# yard-ice-2-fpga.net
KiCad netlist of a schematic drawn in Altium Designer
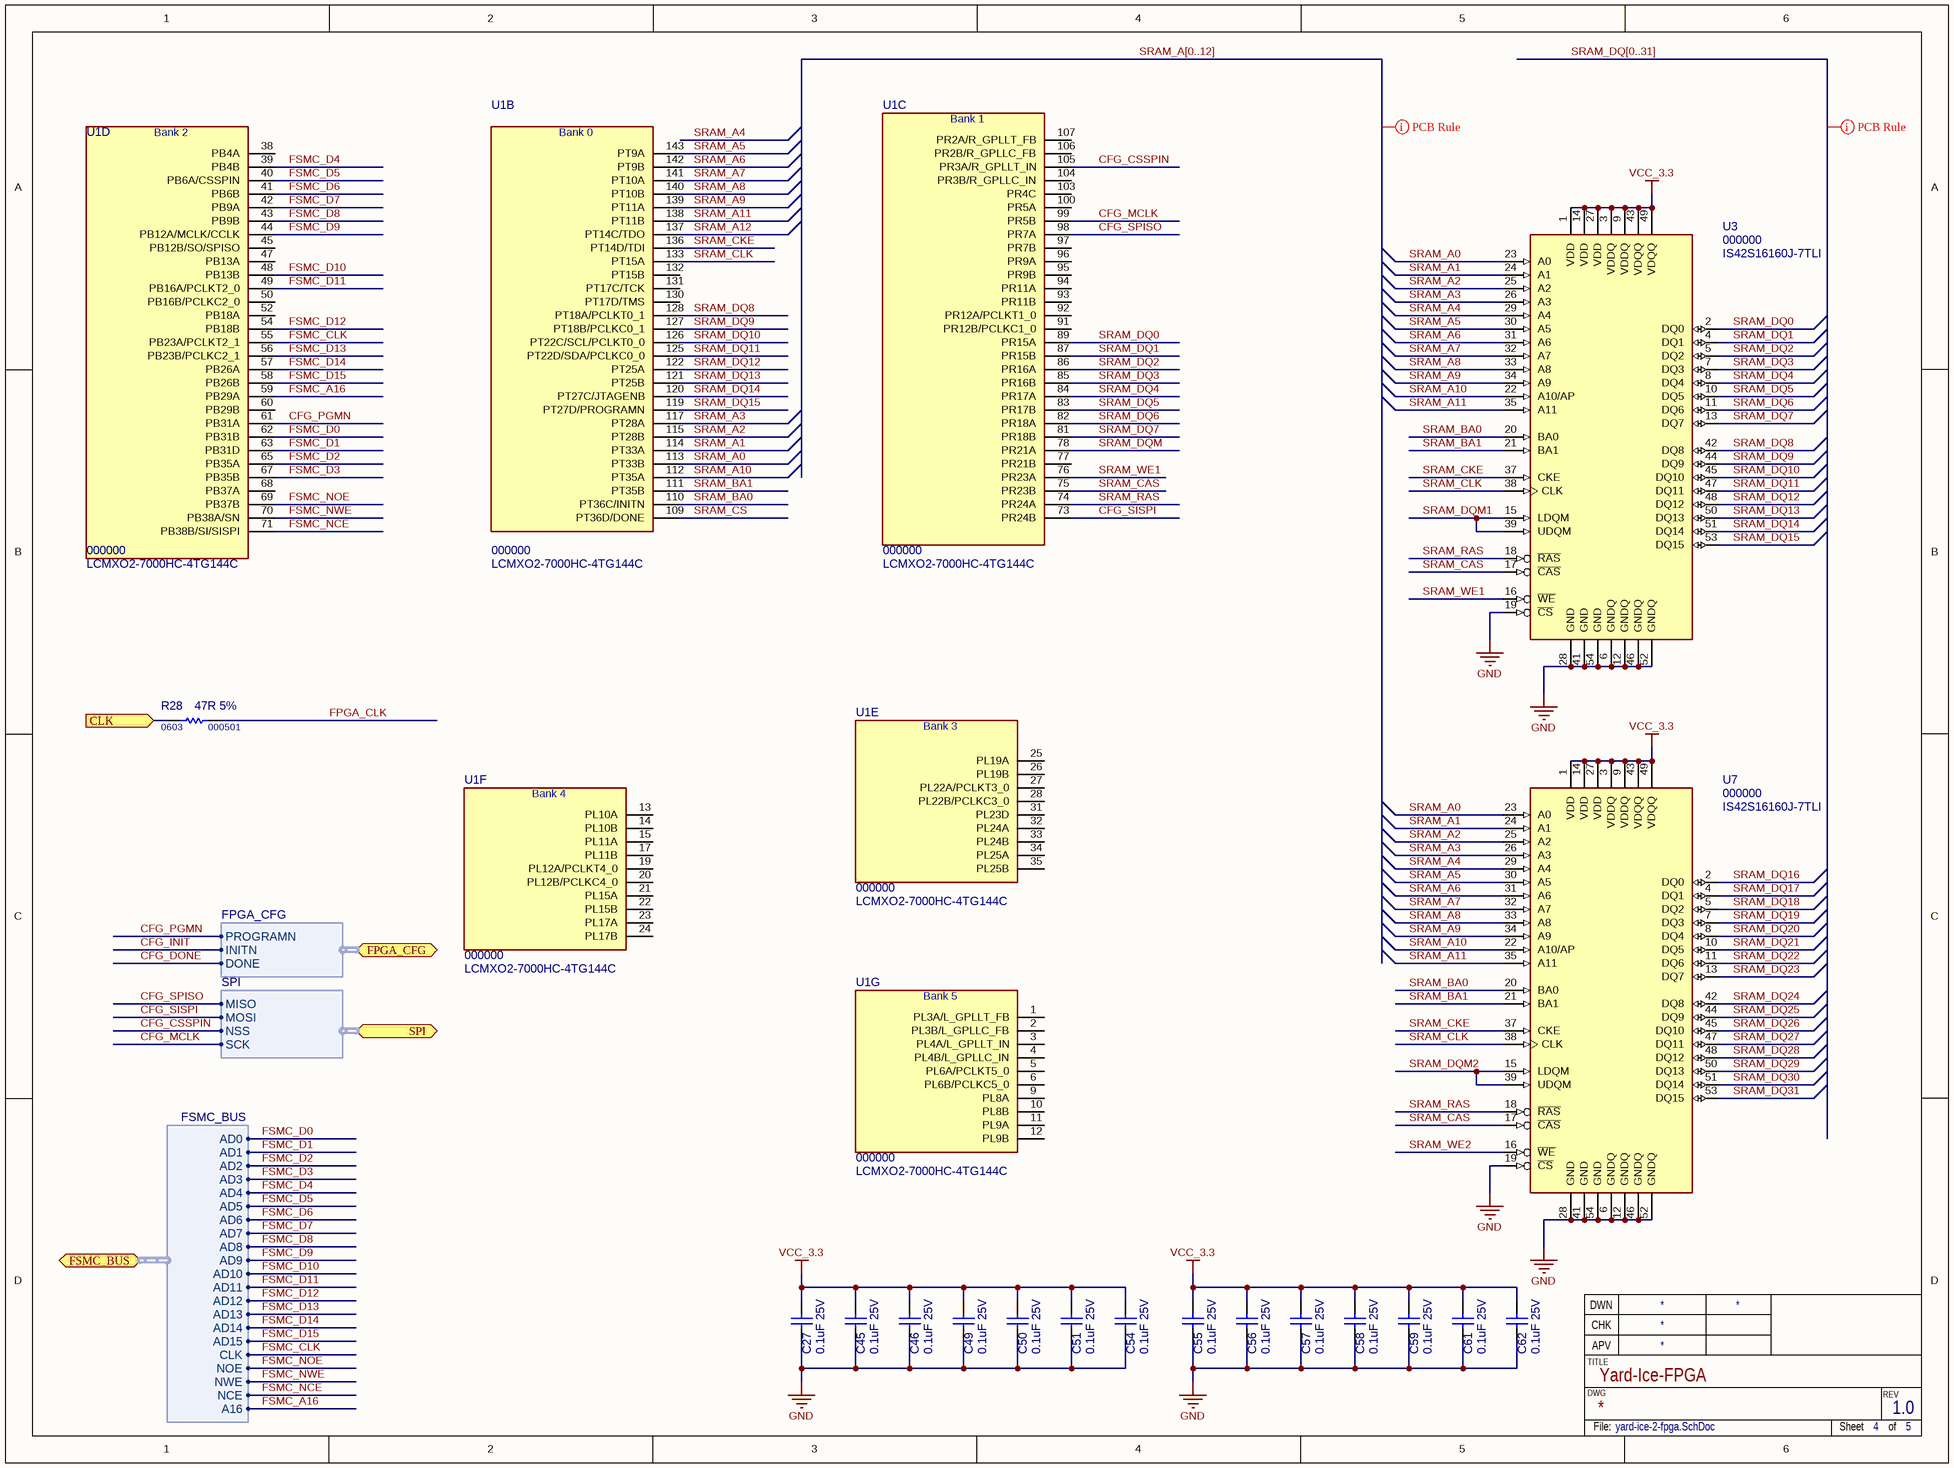
[diagram p0: yard-ice-2-fpga.SchDoc]

(export (version "E")
  (design (tool "Eeschema 10.0.6"))
  (components
    (comp (ref "C27")
      (value "0.1uF 25V")
      (footprint "C0603M")
      (description "SMD Ceramic Chip Capacitor - 0603 - X7R")
      (fields (field (name "MF") "TDK") (field (name "Comment") "000500"))
      (libsource (lib "discrete-sm") (part "C0603"))
    )
    (comp (ref "C45")
      (value "0.1uF 25V")
      (footprint "C0603M")
      (description "SMD Ceramic Chip Capacitor - 0603 - X7R")
      (fields (field (name "MF") "TDK") (field (name "Comment") "000500"))
      (libsource (lib "discrete-sm") (part "C0603"))
    )
    (comp (ref "C46")
      (value "0.1uF 25V")
      (footprint "C0603M")
      (description "SMD Ceramic Chip Capacitor - 0603 - X7R")
      (fields (field (name "MF") "TDK") (field (name "Comment") "000500"))
      (libsource (lib "discrete-sm") (part "C0603"))
    )
    (comp (ref "C49")
      (value "0.1uF 25V")
      (footprint "C0603M")
      (description "SMD Ceramic Chip Capacitor - 0603 - X7R")
      (fields (field (name "MF") "TDK") (field (name "Comment") "000500"))
      (libsource (lib "discrete-sm") (part "C0603"))
    )
    (comp (ref "C50")
      (value "0.1uF 25V")
      (footprint "C0603M")
      (description "SMD Ceramic Chip Capacitor - 0603 - X7R")
      (fields (field (name "MF") "TDK") (field (name "Comment") "000500"))
      (libsource (lib "discrete-sm") (part "C0603"))
    )
    (comp (ref "C51")
      (value "0.1uF 25V")
      (footprint "C0603M")
      (description "SMD Ceramic Chip Capacitor - 0603 - X7R")
      (fields (field (name "MF") "TDK") (field (name "Comment") "000500"))
      (libsource (lib "discrete-sm") (part "C0603"))
    )
    (comp (ref "C54")
      (value "0.1uF 25V")
      (footprint "C0603M")
      (description "SMD Ceramic Chip Capacitor - 0603 - X7R")
      (fields (field (name "MF") "TDK") (field (name "Comment") "000500"))
      (libsource (lib "discrete-sm") (part "C0603"))
    )
    (comp (ref "C55")
      (value "0.1uF 25V")
      (footprint "C0603M")
      (description "SMD Ceramic Chip Capacitor - 0603 - X7R")
      (fields (field (name "MF") "TDK") (field (name "Comment") "000500"))
      (libsource (lib "discrete-sm") (part "C0603"))
    )
    (comp (ref "C56")
      (value "0.1uF 25V")
      (footprint "C0603M")
      (description "SMD Ceramic Chip Capacitor - 0603 - X7R")
      (fields (field (name "MF") "TDK") (field (name "Comment") "000500"))
      (libsource (lib "discrete-sm") (part "C0603"))
    )
    (comp (ref "C57")
      (value "0.1uF 25V")
      (footprint "C0603M")
      (description "SMD Ceramic Chip Capacitor - 0603 - X7R")
      (fields (field (name "MF") "TDK") (field (name "Comment") "000500"))
      (libsource (lib "discrete-sm") (part "C0603"))
    )
    (comp (ref "C58")
      (value "0.1uF 25V")
      (footprint "C0603M")
      (description "SMD Ceramic Chip Capacitor - 0603 - X7R")
      (fields (field (name "MF") "TDK") (field (name "Comment") "000500"))
      (libsource (lib "discrete-sm") (part "C0603"))
    )
    (comp (ref "C59")
      (value "0.1uF 25V")
      (footprint "C0603M")
      (description "SMD Ceramic Chip Capacitor - 0603 - X7R")
      (fields (field (name "MF") "TDK") (field (name "Comment") "000500"))
      (libsource (lib "discrete-sm") (part "C0603"))
    )
    (comp (ref "C61")
      (value "0.1uF 25V")
      (footprint "C0603M")
      (description "SMD Ceramic Chip Capacitor - 0603 - X7R")
      (fields (field (name "MF") "TDK") (field (name "Comment") "000500"))
      (libsource (lib "discrete-sm") (part "C0603"))
    )
    (comp (ref "C62")
      (value "0.1uF 25V")
      (footprint "C0603M")
      (description "SMD Ceramic Chip Capacitor - 0603 - X7R")
      (fields (field (name "MF") "TDK") (field (name "Comment") "000500"))
      (libsource (lib "discrete-sm") (part "C0603"))
    )
    (comp (ref "R28")
      (value "000501")
      (footprint "R0603M")
      (description "SMD Chip Resistor - 0603")
      (fields (field (name "ALTIUM_VALUE") "47R 5%") (field (name "PACKAGE") "0603"))
      (libsource (lib "discrete-sm") (part "R0603"))
    )
    (comp (ref "U1")
      (value "000000")
      (footprint "144-TQFP")
      (description "FPGA, 6864 Logic Elements, Flash")
      (fields (field (name "MF") "Lattice") (field (name "ALTIUM_VALUE") "LCMXO2-7000HC-4TG144C"))
      (libsource (lib "lattice-fpga") (part "LCMXO2-7000HC"))
    )
    (comp (ref "U3")
      (value "000000")
      (footprint "TSOP-54-II")
      (description "256Mbit (16M x16) 143MHz SDRAM")
      (fields (field (name "MF") "ISSI") (field (name "ALTIUM_VALUE") "IS42S16160J-7TLI"))
      (libsource (lib "issi") (part "IS42S16160J-7TL"))
    )
    (comp (ref "U7")
      (value "000000")
      (footprint "TSOP-54-II")
      (description "256Mbit (16M x16) 143MHz SDRAM")
      (fields (field (name "MF") "ISSI") (field (name "ALTIUM_VALUE") "IS42S16160J-7TLI"))
      (libsource (lib "issi") (part "IS42S16160J-7TL"))
    )
  )
  (nets
    (net (code "4") (name "/CFG_CSSPIN") (class "Default")
      (node (ref "U1") (pin "105") (pinfunction "PR3A/R_GPLLT_IN_105") (pintype "passive"))
    )
    (net (code "7") (name "/CFG_MCLK") (class "Default")
      (node (ref "U1") (pin "99") (pinfunction "PR5B_99") (pintype "passive"))
    )
    (net (code "8") (name "/CFG_PGMN") (class "Default")
      (node (ref "U1") (pin "61") (pinfunction "PB31A_61") (pintype "power_in"))
    )
    (net (code "9") (name "/CFG_SISPI") (class "Default")
      (node (ref "U1") (pin "73") (pinfunction "PR24B_73") (pintype "passive"))
    )
    (net (code "10") (name "/CFG_SPISO") (class "Default")
      (node (ref "U1") (pin "98") (pinfunction "PR7A_98") (pintype "passive"))
    )
    (net (code "11") (name "/CLK") (class "Default")
      (node (ref "R28") (pin "2") (pinfunction "2_2") (pintype "passive"))
    )
    (net (code "12") (name "/FPGA_CLK") (class "Default")
      (node (ref "R28") (pin "1") (pinfunction "1_1") (pintype "passive"))
    )
    (net (code "13") (name "/FSMC_A16") (class "Default")
      (node (ref "U1") (pin "59") (pinfunction "PB29A_59") (pintype "passive"))
    )
    (net (code "14") (name "/FSMC_CLK") (class "Default")
      (node (ref "U1") (pin "55") (pinfunction "PB23A/PCLKT2_1_55") (pintype "power_in"))
    )
    (net (code "15") (name "/FSMC_D0") (class "Default")
      (node (ref "U1") (pin "62") (pinfunction "PB31B_62") (pintype "passive"))
    )
    (net (code "16") (name "/FSMC_D1") (class "Default")
      (node (ref "U1") (pin "63") (pinfunction "PB31D_63") (pintype "passive"))
    )
    (net (code "17") (name "/FSMC_D2") (class "Default")
      (node (ref "U1") (pin "65") (pinfunction "PB35A_65") (pintype "passive"))
    )
    (net (code "18") (name "/FSMC_D3") (class "Default")
      (node (ref "U1") (pin "67") (pinfunction "PB35B_67") (pintype "power_in"))
    )
    (net (code "19") (name "/FSMC_D4") (class "Default")
      (node (ref "U1") (pin "39") (pinfunction "PB4B_39") (pintype "power_in"))
    )
    (net (code "20") (name "/FSMC_D5") (class "Default")
      (node (ref "U1") (pin "40") (pinfunction "PB6A/CSSPIN_40") (pintype "passive"))
    )
    (net (code "21") (name "/FSMC_D6") (class "Default")
      (node (ref "U1") (pin "41") (pinfunction "PB6B_41") (pintype "passive"))
    )
    (net (code "22") (name "/FSMC_D7") (class "Default")
      (node (ref "U1") (pin "42") (pinfunction "PB9A_42") (pintype "passive"))
    )
    (net (code "23") (name "/FSMC_D8") (class "Default")
      (node (ref "U1") (pin "43") (pinfunction "PB9B_43") (pintype "passive"))
    )
    (net (code "24") (name "/FSMC_D9") (class "Default")
      (node (ref "U1") (pin "44") (pinfunction "PB12A/MCLK/CCLK_44") (pintype "passive"))
    )
    (net (code "25") (name "/FSMC_D10") (class "Default")
      (node (ref "U1") (pin "48") (pinfunction "PB13B_48") (pintype "passive"))
    )
    (net (code "26") (name "/FSMC_D11") (class "Default")
      (node (ref "U1") (pin "49") (pinfunction "PB16A/PCLKT2_0_49") (pintype "passive"))
    )
    (net (code "27") (name "/FSMC_D12") (class "Default")
      (node (ref "U1") (pin "54") (pinfunction "PB18B_54") (pintype "passive"))
    )
    (net (code "28") (name "/FSMC_D13") (class "Default")
      (node (ref "U1") (pin "56") (pinfunction "PB23B/PCLKC2_1_56") (pintype "passive"))
    )
    (net (code "29") (name "/FSMC_D14") (class "Default")
      (node (ref "U1") (pin "57") (pinfunction "PB26A_57") (pintype "passive"))
    )
    (net (code "30") (name "/FSMC_D15") (class "Default")
      (node (ref "U1") (pin "58") (pinfunction "PB26B_58") (pintype "power_in"))
    )
    (net (code "31") (name "/FSMC_NCE") (class "Default")
      (node (ref "U1") (pin "71") (pinfunction "PB38B/SI/SISPI_71") (pintype "passive"))
    )
    (net (code "32") (name "/FSMC_NOE") (class "Default")
      (node (ref "U1") (pin "69") (pinfunction "PB37B_69") (pintype "passive"))
    )
    (net (code "33") (name "/FSMC_NWE") (class "Default")
      (node (ref "U1") (pin "70") (pinfunction "PB38A/SN_70") (pintype "passive"))
    )
    (net (code "34") (name "/SRAM_A0") (class "Default")
      (node (ref "U1") (pin "113") (pinfunction "PT33B_113") (pintype "passive"))
      (node (ref "U3") (pin "23") (pinfunction "A0_23") (pintype "input"))
      (node (ref "U7") (pin "23") (pinfunction "A0_23") (pintype "input"))
    )
    (net (code "35") (name "/SRAM_A1") (class "Default")
      (node (ref "U1") (pin "114") (pinfunction "PT33A_114") (pintype "passive"))
      (node (ref "U3") (pin "24") (pinfunction "A1_24") (pintype "input"))
      (node (ref "U7") (pin "24") (pinfunction "A1_24") (pintype "input"))
    )
    (net (code "36") (name "/SRAM_A2") (class "Default")
      (node (ref "U1") (pin "115") (pinfunction "PT28B_115") (pintype "passive"))
      (node (ref "U3") (pin "25") (pinfunction "A2_25") (pintype "input"))
      (node (ref "U7") (pin "25") (pinfunction "A2_25") (pintype "input"))
    )
    (net (code "37") (name "/SRAM_A3") (class "Default")
      (node (ref "U1") (pin "117") (pinfunction "PT28A_117") (pintype "passive"))
      (node (ref "U3") (pin "26") (pinfunction "A3_26") (pintype "input"))
      (node (ref "U7") (pin "26") (pinfunction "A3_26") (pintype "input"))
    )
    (net (code "38") (name "/SRAM_A4") (class "Default")
      (node (ref "U3") (pin "29") (pinfunction "A4_29") (pintype "input"))
      (node (ref "U7") (pin "29") (pinfunction "A4_29") (pintype "input"))
    )
    (net (code "39") (name "/SRAM_A5") (class "Default")
      (node (ref "U1") (pin "143") (pinfunction "PT9A_143") (pintype "passive"))
      (node (ref "U3") (pin "30") (pinfunction "A5_30") (pintype "input"))
      (node (ref "U7") (pin "30") (pinfunction "A5_30") (pintype "input"))
    )
    (net (code "40") (name "/SRAM_A6") (class "Default")
      (node (ref "U1") (pin "142") (pinfunction "PT9B_142") (pintype "passive"))
      (node (ref "U3") (pin "31") (pinfunction "A6_31") (pintype "input"))
      (node (ref "U7") (pin "31") (pinfunction "A6_31") (pintype "input"))
    )
    (net (code "41") (name "/SRAM_A7") (class "Default")
      (node (ref "U1") (pin "141") (pinfunction "PT10A_141") (pintype "passive"))
      (node (ref "U3") (pin "32") (pinfunction "A7_32") (pintype "input"))
      (node (ref "U7") (pin "32") (pinfunction "A7_32") (pintype "input"))
    )
    (net (code "42") (name "/SRAM_A8") (class "Default")
      (node (ref "U1") (pin "140") (pinfunction "PT10B_140") (pintype "passive"))
      (node (ref "U3") (pin "33") (pinfunction "A8_33") (pintype "input"))
      (node (ref "U7") (pin "33") (pinfunction "A8_33") (pintype "input"))
    )
    (net (code "43") (name "/SRAM_A9") (class "Default")
      (node (ref "U1") (pin "139") (pinfunction "PT11A_139") (pintype "passive"))
      (node (ref "U3") (pin "34") (pinfunction "A9_34") (pintype "input"))
      (node (ref "U7") (pin "34") (pinfunction "A9_34") (pintype "input"))
    )
    (net (code "44") (name "/SRAM_A10") (class "Default")
      (node (ref "U1") (pin "112") (pinfunction "PT35A_112") (pintype "passive"))
      (node (ref "U3") (pin "22") (pinfunction "A10/AP_22") (pintype "input"))
      (node (ref "U7") (pin "22") (pinfunction "A10/AP_22") (pintype "input"))
    )
    (net (code "45") (name "/SRAM_A11") (class "Default")
      (node (ref "U1") (pin "138") (pinfunction "PT11B_138") (pintype "passive"))
      (node (ref "U3") (pin "35") (pinfunction "A11_35") (pintype "input"))
      (node (ref "U7") (pin "35") (pinfunction "A11_35") (pintype "input"))
    )
    (net (code "46") (name "/SRAM_A12") (class "Default")
      (node (ref "U1") (pin "137") (pinfunction "PT14C/TDO_137") (pintype "passive"))
    )
    (net (code "48") (name "/SRAM_BA0") (class "Default")
      (node (ref "U1") (pin "110") (pinfunction "PT36C/INITN_110") (pintype "passive"))
      (node (ref "U3") (pin "20") (pinfunction "BA0_20") (pintype "input"))
      (node (ref "U7") (pin "20") (pinfunction "BA0_20") (pintype "input"))
    )
    (net (code "49") (name "/SRAM_BA1") (class "Default")
      (node (ref "U1") (pin "111") (pinfunction "PT35B_111") (pintype "passive"))
      (node (ref "U3") (pin "21") (pinfunction "BA1_21") (pintype "input"))
      (node (ref "U7") (pin "21") (pinfunction "BA1_21") (pintype "input"))
    )
    (net (code "50") (name "/SRAM_CAS") (class "Default")
      (node (ref "U1") (pin "75") (pinfunction "PR23B_75") (pintype "power_in"))
      (node (ref "U3") (pin "17") (pinfunction "~{CAS}_17") (pintype "input"))
      (node (ref "U7") (pin "17") (pinfunction "~{CAS}_17") (pintype "input"))
    )
    (net (code "51") (name "/SRAM_CKE") (class "Default")
      (node (ref "U1") (pin "136") (pinfunction "PT14D/TDI_136") (pintype "passive"))
      (node (ref "U3") (pin "37") (pinfunction "CKE_37") (pintype "input"))
      (node (ref "U7") (pin "37") (pinfunction "CKE_37") (pintype "input"))
    )
    (net (code "52") (name "/SRAM_CLK") (class "Default")
      (node (ref "U1") (pin "133") (pinfunction "PT15A_133") (pintype "passive"))
      (node (ref "U3") (pin "38") (pinfunction "CLK_38") (pintype "input"))
      (node (ref "U7") (pin "38") (pinfunction "CLK_38") (pintype "input"))
    )
    (net (code "53") (name "/SRAM_CS") (class "Default")
      (node (ref "U1") (pin "109") (pinfunction "PT36D/DONE_109") (pintype "passive"))
    )
    (net (code "54") (name "/SRAM_DQ0") (class "Default")
      (node (ref "U1") (pin "89") (pinfunction "PR15A_89") (pintype "passive"))
      (node (ref "U3") (pin "2") (pinfunction "DQ0_2") (pintype "bidirectional"))
    )
    (net (code "55") (name "/SRAM_DQ1") (class "Default")
      (node (ref "U1") (pin "87") (pinfunction "PR15B_87") (pintype "passive"))
      (node (ref "U3") (pin "4") (pinfunction "DQ1_4") (pintype "bidirectional"))
    )
    (net (code "56") (name "/SRAM_DQ2") (class "Default")
      (node (ref "U1") (pin "86") (pinfunction "PR16A_86") (pintype "passive"))
      (node (ref "U3") (pin "5") (pinfunction "DQ2_5") (pintype "bidirectional"))
    )
    (net (code "57") (name "/SRAM_DQ3") (class "Default")
      (node (ref "U1") (pin "85") (pinfunction "PR16B_85") (pintype "passive"))
      (node (ref "U3") (pin "7") (pinfunction "DQ3_7") (pintype "bidirectional"))
    )
    (net (code "58") (name "/SRAM_DQ4") (class "Default")
      (node (ref "U1") (pin "84") (pinfunction "PR17A_84") (pintype "passive"))
      (node (ref "U3") (pin "8") (pinfunction "DQ4_8") (pintype "bidirectional"))
    )
    (net (code "59") (name "/SRAM_DQ5") (class "Default")
      (node (ref "U1") (pin "83") (pinfunction "PR17B_83") (pintype "passive"))
      (node (ref "U3") (pin "10") (pinfunction "DQ5_10") (pintype "bidirectional"))
    )
    (net (code "60") (name "/SRAM_DQ6") (class "Default")
      (node (ref "U1") (pin "82") (pinfunction "PR18A_82") (pintype "passive"))
      (node (ref "U3") (pin "11") (pinfunction "DQ6_11") (pintype "bidirectional"))
    )
    (net (code "61") (name "/SRAM_DQ7") (class "Default")
      (node (ref "U1") (pin "81") (pinfunction "PR18B_81") (pintype "passive"))
      (node (ref "U3") (pin "13") (pinfunction "DQ7_13") (pintype "bidirectional"))
    )
    (net (code "62") (name "/SRAM_DQ8") (class "Default")
      (node (ref "U1") (pin "128") (pinfunction "PT18A/PCLKT0_1_128") (pintype "passive"))
      (node (ref "U3") (pin "42") (pinfunction "DQ8_42") (pintype "bidirectional"))
    )
    (net (code "63") (name "/SRAM_DQ9") (class "Default")
      (node (ref "U1") (pin "127") (pinfunction "PT18B/PCLKC0_1_127") (pintype "passive"))
      (node (ref "U3") (pin "44") (pinfunction "DQ9_44") (pintype "bidirectional"))
    )
    (net (code "64") (name "/SRAM_DQ10") (class "Default")
      (node (ref "U1") (pin "126") (pinfunction "PT22C/SCL/PCLKT0_0_126") (pintype "passive"))
      (node (ref "U3") (pin "45") (pinfunction "DQ10_45") (pintype "bidirectional"))
    )
    (net (code "65") (name "/SRAM_DQ11") (class "Default")
      (node (ref "U1") (pin "125") (pinfunction "PT22D/SDA/PCLKC0_0_125") (pintype "passive"))
      (node (ref "U3") (pin "47") (pinfunction "DQ11_47") (pintype "bidirectional"))
    )
    (net (code "66") (name "/SRAM_DQ12") (class "Default")
      (node (ref "U1") (pin "122") (pinfunction "PT25A_122") (pintype "passive"))
      (node (ref "U3") (pin "48") (pinfunction "DQ12_48") (pintype "bidirectional"))
    )
    (net (code "67") (name "/SRAM_DQ13") (class "Default")
      (node (ref "U1") (pin "121") (pinfunction "PT25B_121") (pintype "passive"))
      (node (ref "U3") (pin "50") (pinfunction "DQ13_50") (pintype "bidirectional"))
    )
    (net (code "68") (name "/SRAM_DQ14") (class "Default")
      (node (ref "U1") (pin "120") (pinfunction "PT27C/JTAGENB_120") (pintype "passive"))
      (node (ref "U3") (pin "51") (pinfunction "DQ14_51") (pintype "bidirectional"))
    )
    (net (code "69") (name "/SRAM_DQ15") (class "Default")
      (node (ref "U1") (pin "119") (pinfunction "PT27D/PROGRAMN_119") (pintype "passive"))
      (node (ref "U3") (pin "53") (pinfunction "DQ15_53") (pintype "bidirectional"))
    )
    (net (code "70") (name "/SRAM_DQ16") (class "Default")
      (node (ref "U7") (pin "2") (pinfunction "DQ0_2") (pintype "bidirectional"))
    )
    (net (code "71") (name "/SRAM_DQ17") (class "Default")
      (node (ref "U7") (pin "4") (pinfunction "DQ1_4") (pintype "bidirectional"))
    )
    (net (code "72") (name "/SRAM_DQ18") (class "Default")
      (node (ref "U7") (pin "5") (pinfunction "DQ2_5") (pintype "bidirectional"))
    )
    (net (code "73") (name "/SRAM_DQ19") (class "Default")
      (node (ref "U7") (pin "7") (pinfunction "DQ3_7") (pintype "bidirectional"))
    )
    (net (code "74") (name "/SRAM_DQ20") (class "Default")
      (node (ref "U7") (pin "8") (pinfunction "DQ4_8") (pintype "bidirectional"))
    )
    (net (code "75") (name "/SRAM_DQ21") (class "Default")
      (node (ref "U7") (pin "10") (pinfunction "DQ5_10") (pintype "bidirectional"))
    )
    (net (code "76") (name "/SRAM_DQ22") (class "Default")
      (node (ref "U7") (pin "11") (pinfunction "DQ6_11") (pintype "bidirectional"))
    )
    (net (code "77") (name "/SRAM_DQ23") (class "Default")
      (node (ref "U7") (pin "13") (pinfunction "DQ7_13") (pintype "bidirectional"))
    )
    (net (code "78") (name "/SRAM_DQ24") (class "Default")
      (node (ref "U7") (pin "42") (pinfunction "DQ8_42") (pintype "bidirectional"))
    )
    (net (code "79") (name "/SRAM_DQ25") (class "Default")
      (node (ref "U7") (pin "44") (pinfunction "DQ9_44") (pintype "bidirectional"))
    )
    (net (code "80") (name "/SRAM_DQ26") (class "Default")
      (node (ref "U7") (pin "45") (pinfunction "DQ10_45") (pintype "bidirectional"))
    )
    (net (code "81") (name "/SRAM_DQ27") (class "Default")
      (node (ref "U7") (pin "47") (pinfunction "DQ11_47") (pintype "bidirectional"))
    )
    (net (code "82") (name "/SRAM_DQ28") (class "Default")
      (node (ref "U7") (pin "48") (pinfunction "DQ12_48") (pintype "bidirectional"))
    )
    (net (code "83") (name "/SRAM_DQ29") (class "Default")
      (node (ref "U7") (pin "50") (pinfunction "DQ13_50") (pintype "bidirectional"))
    )
    (net (code "84") (name "/SRAM_DQ30") (class "Default")
      (node (ref "U7") (pin "51") (pinfunction "DQ14_51") (pintype "bidirectional"))
    )
    (net (code "85") (name "/SRAM_DQ31") (class "Default")
      (node (ref "U7") (pin "53") (pinfunction "DQ15_53") (pintype "bidirectional"))
    )
    (net (code "86") (name "/SRAM_DQM") (class "Default")
      (node (ref "U1") (pin "78") (pinfunction "PR21A_78") (pintype "passive"))
    )
    (net (code "87") (name "/SRAM_DQM1") (class "Default")
      (node (ref "U3") (pin "15") (pinfunction "LDQM_15") (pintype "input"))
      (node (ref "U3") (pin "39") (pinfunction "UDQM_39") (pintype "input"))
    )
    (net (code "88") (name "/SRAM_DQM2") (class "Default")
      (node (ref "U7") (pin "15") (pinfunction "LDQM_15") (pintype "input"))
      (node (ref "U7") (pin "39") (pinfunction "UDQM_39") (pintype "input"))
    )
    (net (code "90") (name "/SRAM_RAS") (class "Default")
      (node (ref "U1") (pin "74") (pinfunction "PR24A_74") (pintype "passive"))
      (node (ref "U3") (pin "18") (pinfunction "~{RAS}_18") (pintype "input"))
      (node (ref "U7") (pin "18") (pinfunction "~{RAS}_18") (pintype "input"))
    )
    (net (code "91") (name "/SRAM_WE1") (class "Default")
      (node (ref "U1") (pin "76") (pinfunction "PR23A_76") (pintype "power_in"))
      (node (ref "U3") (pin "16") (pinfunction "~{WE}_16") (pintype "input"))
    )
    (net (code "92") (name "/SRAM_WE2") (class "Default")
      (node (ref "U7") (pin "16") (pinfunction "~{WE}_16") (pintype "input"))
    )
    (net (code "96") (name "GND") (class "Default")
      (node (ref "C27") (pin "2") (pinfunction "2_2") (pintype "passive"))
      (node (ref "C45") (pin "2") (pinfunction "2_2") (pintype "passive"))
      (node (ref "C46") (pin "2") (pinfunction "2_2") (pintype "passive"))
      (node (ref "C49") (pin "2") (pinfunction "2_2") (pintype "passive"))
      (node (ref "C50") (pin "2") (pinfunction "2_2") (pintype "passive"))
      (node (ref "C51") (pin "2") (pinfunction "2_2") (pintype "passive"))
      (node (ref "C54") (pin "2") (pinfunction "2_2") (pintype "passive"))
      (node (ref "C55") (pin "2") (pinfunction "2_2") (pintype "passive"))
      (node (ref "C56") (pin "2") (pinfunction "2_2") (pintype "passive"))
      (node (ref "C57") (pin "2") (pinfunction "2_2") (pintype "passive"))
      (node (ref "C58") (pin "2") (pinfunction "2_2") (pintype "passive"))
      (node (ref "C59") (pin "2") (pinfunction "2_2") (pintype "passive"))
      (node (ref "C61") (pin "2") (pinfunction "2_2") (pintype "passive"))
      (node (ref "C62") (pin "2") (pinfunction "2_2") (pintype "passive"))
      (node (ref "U3") (pin "12") (pinfunction "GNDQ_12") (pintype "power_in"))
      (node (ref "U3") (pin "19") (pinfunction "~{CS}_19") (pintype "input"))
      (node (ref "U3") (pin "28") (pinfunction "GND_28") (pintype "power_in"))
      (node (ref "U3") (pin "41") (pinfunction "GND_41") (pintype "power_in"))
      (node (ref "U3") (pin "46") (pinfunction "GNDQ_46") (pintype "power_in"))
      (node (ref "U3") (pin "52") (pinfunction "GNDQ_52") (pintype "power_in"))
      (node (ref "U3") (pin "54") (pinfunction "GND_54") (pintype "power_in"))
      (node (ref "U3") (pin "6") (pinfunction "GNDQ_6") (pintype "power_in"))
      (node (ref "U7") (pin "12") (pinfunction "GNDQ_12") (pintype "power_in"))
      (node (ref "U7") (pin "19") (pinfunction "~{CS}_19") (pintype "input"))
      (node (ref "U7") (pin "28") (pinfunction "GND_28") (pintype "power_in"))
      (node (ref "U7") (pin "41") (pinfunction "GND_41") (pintype "power_in"))
      (node (ref "U7") (pin "46") (pinfunction "GNDQ_46") (pintype "power_in"))
      (node (ref "U7") (pin "52") (pinfunction "GNDQ_52") (pintype "power_in"))
      (node (ref "U7") (pin "54") (pinfunction "GND_54") (pintype "power_in"))
      (node (ref "U7") (pin "6") (pinfunction "GNDQ_6") (pintype "power_in"))
    )
    (net (code "97") (name "VCC_3.3") (class "Default")
      (node (ref "C27") (pin "1") (pinfunction "1_1") (pintype "passive"))
      (node (ref "C45") (pin "1") (pinfunction "1_1") (pintype "passive"))
      (node (ref "C46") (pin "1") (pinfunction "1_1") (pintype "passive"))
      (node (ref "C49") (pin "1") (pinfunction "1_1") (pintype "passive"))
      (node (ref "C50") (pin "1") (pinfunction "1_1") (pintype "passive"))
      (node (ref "C51") (pin "1") (pinfunction "1_1") (pintype "passive"))
      (node (ref "C54") (pin "1") (pinfunction "1_1") (pintype "passive"))
      (node (ref "C55") (pin "1") (pinfunction "1_1") (pintype "passive"))
      (node (ref "C56") (pin "1") (pinfunction "1_1") (pintype "passive"))
      (node (ref "C57") (pin "1") (pinfunction "1_1") (pintype "passive"))
      (node (ref "C58") (pin "1") (pinfunction "1_1") (pintype "passive"))
      (node (ref "C59") (pin "1") (pinfunction "1_1") (pintype "passive"))
      (node (ref "C61") (pin "1") (pinfunction "1_1") (pintype "passive"))
      (node (ref "C62") (pin "1") (pinfunction "1_1") (pintype "passive"))
      (node (ref "U3") (pin "1") (pinfunction "VDD_1") (pintype "power_in"))
      (node (ref "U3") (pin "14") (pinfunction "VDD_14") (pintype "power_in"))
      (node (ref "U3") (pin "27") (pinfunction "VDD_27") (pintype "power_in"))
      (node (ref "U3") (pin "3") (pinfunction "VDDQ_3") (pintype "power_in"))
      (node (ref "U3") (pin "43") (pinfunction "VDQQ_43") (pintype "power_in"))
      (node (ref "U3") (pin "49") (pinfunction "VDQQ_49") (pintype "power_in"))
      (node (ref "U3") (pin "9") (pinfunction "VDDQ_9") (pintype "power_in"))
      (node (ref "U7") (pin "1") (pinfunction "VDD_1") (pintype "power_in"))
      (node (ref "U7") (pin "14") (pinfunction "VDD_14") (pintype "power_in"))
      (node (ref "U7") (pin "27") (pinfunction "VDD_27") (pintype "power_in"))
      (node (ref "U7") (pin "3") (pinfunction "VDDQ_3") (pintype "power_in"))
      (node (ref "U7") (pin "43") (pinfunction "VDQQ_43") (pintype "power_in"))
      (node (ref "U7") (pin "49") (pinfunction "VDQQ_49") (pintype "power_in"))
      (node (ref "U7") (pin "9") (pinfunction "VDDQ_9") (pintype "power_in"))
    )
    (net (code "98") (name "unconnected-(U1B-PT15B-Pad132)") (class "Default")
      (node (ref "U1") (pin "132") (pinfunction "PT15B_132") (pintype "passive"))
    )
    (net (code "99") (name "unconnected-(U1B-PT17C{slash}TCK-Pad131)") (class "Default")
      (node (ref "U1") (pin "131") (pinfunction "PT17C/TCK_131") (pintype "passive"))
    )
    (net (code "100") (name "unconnected-(U1B-PT17D{slash}TMS-Pad130)") (class "Default")
      (node (ref "U1") (pin "130") (pinfunction "PT17D/TMS_130") (pintype "passive"))
    )
    (net (code "101") (name "unconnected-(U1C-PR2A{slash}R_GPLLT_FB-Pad107)") (class "Default")
      (node (ref "U1") (pin "107") (pinfunction "PR2A/R_GPLLT_FB_107") (pintype "passive"))
    )
    (net (code "102") (name "unconnected-(U1C-PR2B{slash}R_GPLLC_FB-Pad106)") (class "Default")
      (node (ref "U1") (pin "106") (pinfunction "PR2B/R_GPLLC_FB_106") (pintype "passive"))
    )
    (net (code "103") (name "unconnected-(U1C-PR3B{slash}R_GPLLC_IN-Pad104)") (class "Default")
      (node (ref "U1") (pin "104") (pinfunction "PR3B/R_GPLLC_IN_104") (pintype "passive"))
    )
    (net (code "104") (name "unconnected-(U1C-PR4C-Pad103)") (class "Default")
      (node (ref "U1") (pin "103") (pinfunction "PR4C_103") (pintype "passive"))
    )
    (net (code "105") (name "unconnected-(U1C-PR5A-Pad100)") (class "Default")
      (node (ref "U1") (pin "100") (pinfunction "PR5A_100") (pintype "passive"))
    )
    (net (code "106") (name "unconnected-(U1C-PR7B-Pad97)") (class "Default")
      (node (ref "U1") (pin "97") (pinfunction "PR7B_97") (pintype "passive"))
    )
    (net (code "107") (name "unconnected-(U1C-PR9A-Pad96)") (class "Default")
      (node (ref "U1") (pin "96") (pinfunction "PR9A_96") (pintype "passive"))
    )
    (net (code "108") (name "unconnected-(U1C-PR9B-Pad95)") (class "Default")
      (node (ref "U1") (pin "95") (pinfunction "PR9B_95") (pintype "passive"))
    )
    (net (code "109") (name "unconnected-(U1C-PR11A-Pad94)") (class "Default")
      (node (ref "U1") (pin "94") (pinfunction "PR11A_94") (pintype "passive"))
    )
    (net (code "110") (name "unconnected-(U1C-PR11B-Pad93)") (class "Default")
      (node (ref "U1") (pin "93") (pinfunction "PR11B_93") (pintype "passive"))
    )
    (net (code "111") (name "unconnected-(U1C-PR12A{slash}PCLKT1_0-Pad92)") (class "Default")
      (node (ref "U1") (pin "92") (pinfunction "PR12A/PCLKT1_0_92") (pintype "power_in"))
    )
    (net (code "112") (name "unconnected-(U1C-PR12B{slash}PCLKC1_0-Pad91)") (class "Default")
      (node (ref "U1") (pin "91") (pinfunction "PR12B/PCLKC1_0_91") (pintype "passive"))
    )
    (net (code "113") (name "unconnected-(U1C-PR21B-Pad77)") (class "Default")
      (node (ref "U1") (pin "77") (pinfunction "PR21B_77") (pintype "power_in"))
    )
    (net (code "114") (name "unconnected-(U1D-PB4A-Pad38)") (class "Default")
      (node (ref "U1") (pin "38") (pinfunction "PB4A_38") (pintype "power_in"))
    )
    (net (code "115") (name "unconnected-(U1D-PB12B{slash}SO{slash}SPISO-Pad45)") (class "Default")
      (node (ref "U1") (pin "45") (pinfunction "PB12B/SO/SPISO_45") (pintype "passive"))
    )
    (net (code "116") (name "unconnected-(U1D-PB13A-Pad47)") (class "Default")
      (node (ref "U1") (pin "47") (pinfunction "PB13A_47") (pintype "power_in"))
    )
    (net (code "117") (name "unconnected-(U1D-PB16B{slash}PCLKC2_0-Pad50)") (class "Default")
      (node (ref "U1") (pin "50") (pinfunction "PB16B/PCLKC2_0_50") (pintype "passive"))
    )
    (net (code "118") (name "unconnected-(U1D-PB18A-Pad52)") (class "Default")
      (node (ref "U1") (pin "52") (pinfunction "PB18A_52") (pintype "passive"))
    )
    (net (code "119") (name "unconnected-(U1D-PB29B-Pad60)") (class "Default")
      (node (ref "U1") (pin "60") (pinfunction "PB29B_60") (pintype "passive"))
    )
    (net (code "120") (name "unconnected-(U1D-PB37A-Pad68)") (class "Default")
      (node (ref "U1") (pin "68") (pinfunction "PB37A_68") (pintype "passive"))
    )
    (net (code "121") (name "unconnected-(U1E-PL19A-Pad25)") (class "Default")
      (node (ref "U1") (pin "25") (pinfunction "PL19A_25") (pintype "passive"))
    )
    (net (code "122") (name "unconnected-(U1E-PL19B-Pad26)") (class "Default")
      (node (ref "U1") (pin "26") (pinfunction "PL19B_26") (pintype "passive"))
    )
    (net (code "123") (name "unconnected-(U1E-PL22A{slash}PCLKT3_0-Pad27)") (class "Default")
      (node (ref "U1") (pin "27") (pinfunction "PL22A/PCLKT3_0_27") (pintype "passive"))
    )
    (net (code "124") (name "unconnected-(U1E-PL22B{slash}PCLKC3_0-Pad28)") (class "Default")
      (node (ref "U1") (pin "28") (pinfunction "PL22B/PCLKC3_0_28") (pintype "passive"))
    )
    (net (code "125") (name "unconnected-(U1E-PL23D-Pad31)") (class "Default")
      (node (ref "U1") (pin "31") (pinfunction "PL23D_31") (pintype "power_in"))
    )
    (net (code "126") (name "unconnected-(U1E-PL24A-Pad32)") (class "Default")
      (node (ref "U1") (pin "32") (pinfunction "PL24A_32") (pintype "power_in"))
    )
    (net (code "127") (name "unconnected-(U1E-PL24B-Pad33)") (class "Default")
      (node (ref "U1") (pin "33") (pinfunction "PL24B_33") (pintype "passive"))
    )
    (net (code "128") (name "unconnected-(U1E-PL25A-Pad34)") (class "Default")
      (node (ref "U1") (pin "34") (pinfunction "PL25A_34") (pintype "passive"))
    )
    (net (code "129") (name "unconnected-(U1E-PL25B-Pad35)") (class "Default")
      (node (ref "U1") (pin "35") (pinfunction "PL25B_35") (pintype "power_in"))
    )
    (net (code "130") (name "unconnected-(U1F-PL10A-Pad13)") (class "Default")
      (node (ref "U1") (pin "13") (pinfunction "PL10A_13") (pintype "passive"))
    )
    (net (code "131") (name "unconnected-(U1F-PL10B-Pad14)") (class "Default")
      (node (ref "U1") (pin "14") (pinfunction "PL10B_14") (pintype "passive"))
    )
    (net (code "132") (name "unconnected-(U1F-PL11A-Pad15)") (class "Default")
      (node (ref "U1") (pin "15") (pinfunction "PL11A_15") (pintype "passive"))
    )
    (net (code "133") (name "unconnected-(U1F-PL11B-Pad17)") (class "Default")
      (node (ref "U1") (pin "17") (pinfunction "PL11B_17") (pintype "passive"))
    )
    (net (code "134") (name "unconnected-(U1F-PL12A{slash}PCLKT4_0-Pad19)") (class "Default")
      (node (ref "U1") (pin "19") (pinfunction "PL12A/PCLKT4_0_19") (pintype "passive"))
    )
    (net (code "135") (name "unconnected-(U1F-PL12B{slash}PCLKC4_0-Pad20)") (class "Default")
      (node (ref "U1") (pin "20") (pinfunction "PL12B/PCLKC4_0_20") (pintype "passive"))
    )
    (net (code "136") (name "unconnected-(U1F-PL15A-Pad21)") (class "Default")
      (node (ref "U1") (pin "21") (pinfunction "PL15A_21") (pintype "passive"))
    )
    (net (code "137") (name "unconnected-(U1F-PL15B-Pad22)") (class "Default")
      (node (ref "U1") (pin "22") (pinfunction "PL15B_22") (pintype "passive"))
    )
    (net (code "138") (name "unconnected-(U1F-PL17A-Pad23)") (class "Default")
      (node (ref "U1") (pin "23") (pinfunction "PL17A_23") (pintype "passive"))
    )
    (net (code "139") (name "unconnected-(U1F-PL17B-Pad24)") (class "Default")
      (node (ref "U1") (pin "24") (pinfunction "PL17B_24") (pintype "passive"))
    )
    (net (code "140") (name "unconnected-(U1G-PL3A{slash}L_GPLLT_FB-Pad1)") (class "Default")
      (node (ref "U1") (pin "1") (pinfunction "PL3A/L_GPLLT_FB_1") (pintype "passive"))
    )
    (net (code "141") (name "unconnected-(U1G-PL3B{slash}L_GPLLC_FB-Pad2)") (class "Default")
      (node (ref "U1") (pin "2") (pinfunction "PL3B/L_GPLLC_FB_2") (pintype "passive"))
    )
    (net (code "142") (name "unconnected-(U1G-PL4A{slash}L_GPLLT_IN-Pad3)") (class "Default")
      (node (ref "U1") (pin "3") (pinfunction "PL4A/L_GPLLT_IN_3") (pintype "passive"))
    )
    (net (code "143") (name "unconnected-(U1G-PL4B{slash}L_GPLLC_IN-Pad4)") (class "Default")
      (node (ref "U1") (pin "4") (pinfunction "PL4B/L_GPLLC_IN_4") (pintype "passive"))
    )
    (net (code "144") (name "unconnected-(U1G-PL6A{slash}PCLKT5_0-Pad5)") (class "Default")
      (node (ref "U1") (pin "5") (pinfunction "PL6A/PCLKT5_0_5") (pintype "power_in"))
    )
    (net (code "145") (name "unconnected-(U1G-PL6B{slash}PCLKC5_0-Pad6)") (class "Default")
      (node (ref "U1") (pin "6") (pinfunction "PL6B/PCLKC5_0_6") (pintype "passive"))
    )
    (net (code "146") (name "unconnected-(U1G-PL8A-Pad9)") (class "Default")
      (node (ref "U1") (pin "9") (pinfunction "PL8A_9") (pintype "passive"))
    )
    (net (code "147") (name "unconnected-(U1G-PL8B-Pad10)") (class "Default")
      (node (ref "U1") (pin "10") (pinfunction "PL8B_10") (pintype "passive"))
    )
    (net (code "148") (name "unconnected-(U1G-PL9A-Pad11)") (class "Default")
      (node (ref "U1") (pin "11") (pinfunction "PL9A_11") (pintype "power_in"))
    )
    (net (code "149") (name "unconnected-(U1G-PL9B-Pad12)") (class "Default")
      (node (ref "U1") (pin "12") (pinfunction "PL9B_12") (pintype "passive"))
    )
  )
)
